# badge.net
KiCad netlist of a schematic drawn in EAGLE
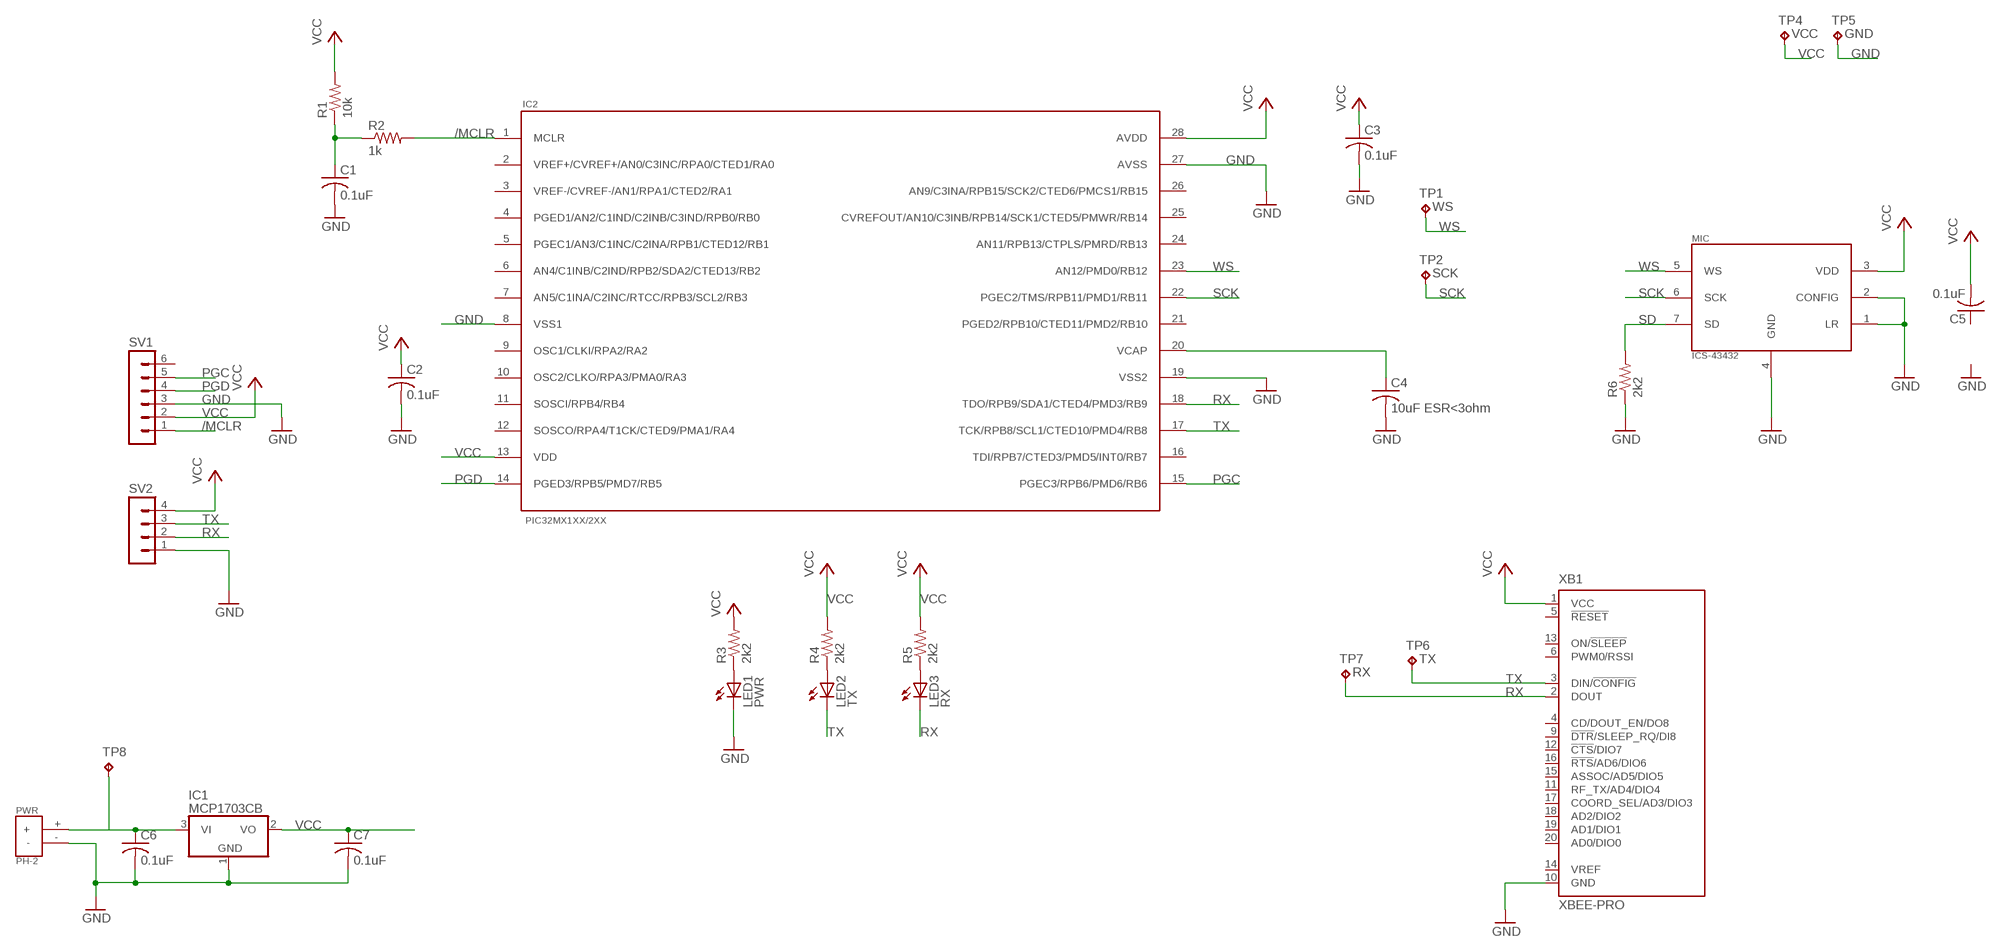
[diagram p0: schematic, sheet 1]

(export (version "E")
  (design (tool "Eeschema 10.0.6"))
  (components
    (comp (ref "C1")
      (value "0.1uF")
      (footprint "eagle-import:C0603")
      (libsource (lib "eagle-import") (part "C-USC0603"))
    )
    (comp (ref "C2")
      (value "0.1uF")
      (footprint "eagle-import:C0603")
      (libsource (lib "eagle-import") (part "C-USC0603"))
    )
    (comp (ref "C3")
      (value "0.1uF")
      (footprint "eagle-import:C0603")
      (libsource (lib "eagle-import") (part "C-USC0603"))
    )
    (comp (ref "C4")
      (value "10uF ESR<3ohm")
      (footprint "eagle-import:C0603")
      (libsource (lib "eagle-import") (part "C-USC0603"))
    )
    (comp (ref "C5")
      (value "0.1uF")
      (footprint "eagle-import:C0603")
      (libsource (lib "eagle-import") (part "C-USC0603"))
    )
    (comp (ref "C6")
      (value "0.1uF")
      (footprint "eagle-import:C0603")
      (libsource (lib "eagle-import") (part "C-USC0603"))
    )
    (comp (ref "C7")
      (value "0.1uF")
      (footprint "eagle-import:C0603")
      (libsource (lib "eagle-import") (part "C-USC0603"))
    )
    (comp (ref "IC1")
      (value "MCP1703CB")
      (footprint "eagle-import:SOT23")
      (libsource (lib "eagle-import") (part "MCP1703CB"))
    )
    (comp (ref "IC2")
      (value "PIC32MX1XX/2XX")
      (footprint "eagle-import:SOIC-28")
      (libsource (lib "eagle-import") (part "PIC32MX1XX/2XX"))
    )
    (comp (ref "LED1")
      (value "PWR")
      (footprint "eagle-import:CHIP-LED0603")
      (libsource (lib "eagle-import") (part "LEDCHIP-LED0603"))
    )
    (comp (ref "LED2")
      (value "TX")
      (footprint "eagle-import:CHIP-LED0603")
      (libsource (lib "eagle-import") (part "LEDCHIP-LED0603"))
    )
    (comp (ref "LED3")
      (value "RX")
      (footprint "eagle-import:CHIP-LED0603")
      (libsource (lib "eagle-import") (part "LEDCHIP-LED0603"))
    )
    (comp (ref "MIC")
      (value "ICS-43432")
      (footprint "eagle-import:ICS-43432")
      (libsource (lib "eagle-import") (part "ICS-43432"))
    )
    (comp (ref "PWR")
      (value "PH-2")
      (footprint "eagle-import:PH-2")
      (libsource (lib "eagle-import") (part "PH-2"))
    )
    (comp (ref "R1")
      (value "10k")
      (footprint "eagle-import:R0603")
      (libsource (lib "eagle-import") (part "R-US_R0603"))
    )
    (comp (ref "R2")
      (value "1k")
      (footprint "eagle-import:R0603")
      (libsource (lib "eagle-import") (part "R-US_R0603"))
    )
    (comp (ref "R3")
      (value "2k2")
      (footprint "eagle-import:R0603")
      (libsource (lib "eagle-import") (part "R-US_R0603"))
    )
    (comp (ref "R4")
      (value "2k2")
      (footprint "eagle-import:R0603")
      (libsource (lib "eagle-import") (part "R-US_R0603"))
    )
    (comp (ref "R5")
      (value "2k2")
      (footprint "eagle-import:R0603")
      (libsource (lib "eagle-import") (part "R-US_R0603"))
    )
    (comp (ref "R6")
      (value "2k2")
      (footprint "eagle-import:R0603")
      (libsource (lib "eagle-import") (part "R-US_R0603"))
    )
    (comp (ref "SV1")
      (value "MA06-1")
      (footprint "eagle-import:MA06-1")
      (libsource (lib "eagle-import") (part "MA06-1"))
    )
    (comp (ref "SV2")
      (value "MA04-1")
      (footprint "eagle-import:MA04-1")
      (libsource (lib "eagle-import") (part "MA04-1"))
    )
    (comp (ref "TP1")
      (value "TPPAD1-13")
      (footprint "eagle-import:P1-13")
      (fields (field (name "TP_SIGNAL_NAME") "WS"))
      (libsource (lib "eagle-import") (part "TPPAD1-13"))
    )
    (comp (ref "TP2")
      (value "TPPAD1-13")
      (footprint "eagle-import:P1-13")
      (fields (field (name "TP_SIGNAL_NAME") "SCK"))
      (libsource (lib "eagle-import") (part "TPPAD1-13"))
    )
    (comp (ref "TP4")
      (value "TPPAD1-13")
      (footprint "eagle-import:P1-13")
      (fields (field (name "TP_SIGNAL_NAME") "VCC"))
      (libsource (lib "eagle-import") (part "TPPAD1-13"))
    )
    (comp (ref "TP5")
      (value "TPPAD1-13")
      (footprint "eagle-import:P1-13")
      (fields (field (name "TP_SIGNAL_NAME") "GND"))
      (libsource (lib "eagle-import") (part "TPPAD1-13"))
    )
    (comp (ref "TP6")
      (value "TPPAD1-13")
      (footprint "eagle-import:P1-13")
      (fields (field (name "TP_SIGNAL_NAME") "TX"))
      (libsource (lib "eagle-import") (part "TPPAD1-13"))
    )
    (comp (ref "TP7")
      (value "TPPAD1-13")
      (footprint "eagle-import:P1-13")
      (fields (field (name "TP_SIGNAL_NAME") "RX"))
      (libsource (lib "eagle-import") (part "TPPAD1-13"))
    )
    (comp (ref "TP8")
      (value "TPPAD1-13")
      (footprint "eagle-import:P1-13")
      (fields (field (name "TP_SIGNAL_NAME") "PWR"))
      (libsource (lib "eagle-import") (part "TPPAD1-13"))
    )
    (comp (ref "XB1")
      (value "XBEE-PRO")
      (footprint "eagle-import:XBEE-PRO")
      (fields (field (name "MPN") "XBP24-AWI-001"))
      (libsource (lib "eagle-import") (part "XBEE-PRO"))
    )
  )
  (nets
    (net (code "1") (name "/PGC") (class "Default")
      (node (ref "IC2") (pin "15") (pinfunction "PGEC3/RPB6/PMD6/RB6_15") (pintype "bidirectional"))
      (node (ref "SV1") (pin "5") (pinfunction "5_5") (pintype "passive"))
    )
    (net (code "2") (name "/PGD") (class "Default")
      (node (ref "IC2") (pin "14") (pinfunction "PGED3/RPB5/PMD7/RB5_14") (pintype "bidirectional"))
      (node (ref "SV1") (pin "4") (pinfunction "4_4") (pintype "passive"))
    )
    (net (code "3") (name "/RX") (class "Default")
      (node (ref "IC2") (pin "18") (pinfunction "TDO/RPB9/SDA1/CTED4/PMD3/RB9_18") (pintype "bidirectional"))
      (node (ref "LED3") (pin "C") (pinfunction "C_C") (pintype "passive"))
      (node (ref "SV2") (pin "2") (pinfunction "2_2") (pintype "passive"))
      (node (ref "TP7") (pin "TP") (pinfunction "TP_TP") (pintype "input"))
      (node (ref "XB1") (pin "2") (pinfunction "DOUT_2") (pintype "output"))
    )
    (net (code "4") (name "/SCK") (class "Default")
      (node (ref "IC2") (pin "22") (pinfunction "PGEC2/TMS/RPB11/PMD1/RB11_22") (pintype "bidirectional"))
      (node (ref "MIC") (pin "6") (pinfunction "SCK_6") (pintype "bidirectional"))
      (node (ref "TP2") (pin "TP") (pinfunction "TP_TP") (pintype "input"))
    )
    (net (code "5") (name "/SD") (class "Default")
      (node (ref "MIC") (pin "7") (pinfunction "SD_7") (pintype "bidirectional"))
      (node (ref "R6") (pin "2") (pinfunction "2_2") (pintype "passive"))
    )
    (net (code "6") (name "/TX") (class "Default")
      (node (ref "IC2") (pin "17") (pinfunction "TCK/RPB8/SCL1/CTED10/PMD4/RB8_17") (pintype "bidirectional"))
      (node (ref "LED2") (pin "C") (pinfunction "C_C") (pintype "passive"))
      (node (ref "SV2") (pin "3") (pinfunction "3_3") (pintype "passive"))
      (node (ref "TP6") (pin "TP") (pinfunction "TP_TP") (pintype "input"))
      (node (ref "XB1") (pin "3") (pinfunction "DIN/~{CONFIG}_3") (pintype "input"))
    )
    (net (code "7") (name "/WS") (class "Default")
      (node (ref "IC2") (pin "23") (pinfunction "AN12/PMD0/RB12_23") (pintype "bidirectional"))
      (node (ref "MIC") (pin "5") (pinfunction "WS_5") (pintype "bidirectional"))
      (node (ref "TP1") (pin "TP") (pinfunction "TP_TP") (pintype "input"))
    )
    (net (code "8") (name "/{slash}MCLR") (class "Default")
      (node (ref "IC2") (pin "1") (pinfunction "MCLR_1") (pintype "bidirectional"))
      (node (ref "R2") (pin "2") (pinfunction "2_2") (pintype "passive"))
      (node (ref "SV1") (pin "1") (pinfunction "1_1") (pintype "passive"))
    )
    (net (code "9") (name "GND") (class "Default")
      (node (ref "C1") (pin "2") (pinfunction "2_2") (pintype "passive"))
      (node (ref "C2") (pin "2") (pinfunction "2_2") (pintype "passive"))
      (node (ref "C3") (pin "2") (pinfunction "2_2") (pintype "passive"))
      (node (ref "C4") (pin "2") (pinfunction "2_2") (pintype "passive"))
      (node (ref "C6") (pin "2") (pinfunction "2_2") (pintype "passive"))
      (node (ref "C7") (pin "2") (pinfunction "2_2") (pintype "passive"))
      (node (ref "IC1") (pin "1") (pinfunction "GND_1") (pintype "passive"))
      (node (ref "IC2") (pin "19") (pinfunction "VSS2_19") (pintype "bidirectional"))
      (node (ref "IC2") (pin "27") (pinfunction "AVSS_27") (pintype "bidirectional"))
      (node (ref "IC2") (pin "8") (pinfunction "VSS1_8") (pintype "bidirectional"))
      (node (ref "LED1") (pin "C") (pinfunction "C_C") (pintype "passive"))
      (node (ref "MIC") (pin "1") (pinfunction "LR_1") (pintype "bidirectional"))
      (node (ref "MIC") (pin "2") (pinfunction "CONFIG_2") (pintype "bidirectional"))
      (node (ref "MIC") (pin "4") (pinfunction "GND_4") (pintype "bidirectional"))
      (node (ref "PWR") (pin "-") (pinfunction "-_-") (pintype "bidirectional"))
      (node (ref "R6") (pin "1") (pinfunction "1_1") (pintype "passive"))
      (node (ref "SV1") (pin "3") (pinfunction "3_3") (pintype "passive"))
      (node (ref "SV2") (pin "1") (pinfunction "1_1") (pintype "passive"))
      (node (ref "TP5") (pin "TP") (pinfunction "TP_TP") (pintype "input"))
      (node (ref "XB1") (pin "10") (pinfunction "GND_10") (pintype "power_in"))
    )
    (net (code "10") (name "Net-(C1-Pad1)") (class "Default")
      (node (ref "C1") (pin "1") (pinfunction "1_1") (pintype "passive"))
      (node (ref "R1") (pin "1") (pinfunction "1_1") (pintype "passive"))
      (node (ref "R2") (pin "1") (pinfunction "1_1") (pintype "passive"))
    )
    (net (code "11") (name "Net-(IC1-VI)") (class "Default")
      (node (ref "C6") (pin "1") (pinfunction "1_1") (pintype "passive"))
      (node (ref "IC1") (pin "3") (pinfunction "VI_3") (pintype "input"))
      (node (ref "PWR") (pin "+") (pinfunction "+_+") (pintype "bidirectional"))
      (node (ref "TP8") (pin "TP") (pinfunction "TP_TP") (pintype "input"))
    )
    (net (code "12") (name "Net-(IC2-VCAP)") (class "Default")
      (node (ref "C4") (pin "1") (pinfunction "1_1") (pintype "passive"))
      (node (ref "IC2") (pin "20") (pinfunction "VCAP_20") (pintype "bidirectional"))
    )
    (net (code "13") (name "Net-(LED1-PadA)") (class "Default")
      (node (ref "LED1") (pin "A") (pinfunction "A_A") (pintype "passive"))
      (node (ref "R3") (pin "1") (pinfunction "1_1") (pintype "passive"))
    )
    (net (code "14") (name "Net-(LED2-PadA)") (class "Default")
      (node (ref "LED2") (pin "A") (pinfunction "A_A") (pintype "passive"))
      (node (ref "R4") (pin "1") (pinfunction "1_1") (pintype "passive"))
    )
    (net (code "15") (name "Net-(LED3-PadA)") (class "Default")
      (node (ref "LED3") (pin "A") (pinfunction "A_A") (pintype "passive"))
      (node (ref "R5") (pin "1") (pinfunction "1_1") (pintype "passive"))
    )
    (net (code "16") (name "VCC") (class "Default")
      (node (ref "C2") (pin "1") (pinfunction "1_1") (pintype "passive"))
      (node (ref "C3") (pin "1") (pinfunction "1_1") (pintype "passive"))
      (node (ref "C5") (pin "2") (pinfunction "2_2") (pintype "passive"))
      (node (ref "C7") (pin "1") (pinfunction "1_1") (pintype "passive"))
      (node (ref "IC1") (pin "2") (pinfunction "VO_2") (pintype "passive"))
      (node (ref "IC2") (pin "13") (pinfunction "VDD_13") (pintype "bidirectional"))
      (node (ref "IC2") (pin "28") (pinfunction "AVDD_28") (pintype "bidirectional"))
      (node (ref "MIC") (pin "3") (pinfunction "VDD_3") (pintype "bidirectional"))
      (node (ref "R1") (pin "2") (pinfunction "2_2") (pintype "passive"))
      (node (ref "R3") (pin "2") (pinfunction "2_2") (pintype "passive"))
      (node (ref "R4") (pin "2") (pinfunction "2_2") (pintype "passive"))
      (node (ref "R5") (pin "2") (pinfunction "2_2") (pintype "passive"))
      (node (ref "SV1") (pin "2") (pinfunction "2_2") (pintype "passive"))
      (node (ref "SV2") (pin "4") (pinfunction "4_4") (pintype "passive"))
      (node (ref "TP4") (pin "TP") (pinfunction "TP_TP") (pintype "input"))
      (node (ref "XB1") (pin "1") (pinfunction "VCC_1") (pintype "power_in"))
    )
    (net (code "17") (name "unconnected-(C5-Pad1)") (class "Default")
      (node (ref "C5") (pin "1") (pinfunction "1_1") (pintype "passive"))
    )
    (net (code "18") (name "unconnected-(IC2-AN4{slash}C1INB{slash}C2IND{slash}RPB2{slash}SDA2{slash}CTED13{slash}RB2-Pad6)") (class "Default")
      (node (ref "IC2") (pin "6") (pinfunction "AN4/C1INB/C2IND/RPB2/SDA2/CTED13/RB2_6") (pintype "bidirectional"))
    )
    (net (code "19") (name "unconnected-(IC2-AN5{slash}C1INA{slash}C2INC{slash}RTCC{slash}RPB3{slash}SCL2{slash}RB3-Pad7)") (class "Default")
      (node (ref "IC2") (pin "7") (pinfunction "AN5/C1INA/C2INC/RTCC/RPB3/SCL2/RB3_7") (pintype "bidirectional"))
    )
    (net (code "20") (name "unconnected-(IC2-AN9{slash}C3INA{slash}RPB15{slash}SCK2{slash}CTED6{slash}PMCS1{slash}RB15-Pad26)") (class "Default")
      (node (ref "IC2") (pin "26") (pinfunction "AN9/C3INA/RPB15/SCK2/CTED6/PMCS1/RB15_26") (pintype "bidirectional"))
    )
    (net (code "21") (name "unconnected-(IC2-AN11{slash}RPB13{slash}CTPLS{slash}PMRD{slash}RB13-Pad24)") (class "Default")
      (node (ref "IC2") (pin "24") (pinfunction "AN11/RPB13/CTPLS/PMRD/RB13_24") (pintype "bidirectional"))
    )
    (net (code "22") (name "unconnected-(IC2-CVREFOUT{slash}AN10{slash}C3INB{slash}RPB14{slash}SCK1{slash}CTED5{slash}PMWR{slash}RB14-Pad25)") (class "Default")
      (node (ref "IC2") (pin "25") (pinfunction "CVREFOUT/AN10/C3INB/RPB14/SCK1/CTED5/PMWR/RB14_25") (pintype "bidirectional"))
    )
    (net (code "23") (name "unconnected-(IC2-OSC1{slash}CLKI{slash}RPA2{slash}RA2-Pad9)") (class "Default")
      (node (ref "IC2") (pin "9") (pinfunction "OSC1/CLKI/RPA2/RA2_9") (pintype "bidirectional"))
    )
    (net (code "24") (name "unconnected-(IC2-OSC2{slash}CLKO{slash}RPA3{slash}PMA0{slash}RA3-Pad10)") (class "Default")
      (node (ref "IC2") (pin "10") (pinfunction "OSC2/CLKO/RPA3/PMA0/RA3_10") (pintype "bidirectional"))
    )
    (net (code "25") (name "unconnected-(IC2-PGEC1{slash}AN3{slash}C1INC{slash}C2INA{slash}RPB1{slash}CTED12{slash}RB1-Pad5)") (class "Default")
      (node (ref "IC2") (pin "5") (pinfunction "PGEC1/AN3/C1INC/C2INA/RPB1/CTED12/RB1_5") (pintype "bidirectional"))
    )
    (net (code "26") (name "unconnected-(IC2-PGED1{slash}AN2{slash}C1IND{slash}C2INB{slash}C3IND{slash}RPB0{slash}RB0-Pad4)") (class "Default")
      (node (ref "IC2") (pin "4") (pinfunction "PGED1/AN2/C1IND/C2INB/C3IND/RPB0/RB0_4") (pintype "bidirectional"))
    )
    (net (code "27") (name "unconnected-(IC2-PGED2{slash}RPB10{slash}CTED11{slash}PMD2{slash}RB10-Pad21)") (class "Default")
      (node (ref "IC2") (pin "21") (pinfunction "PGED2/RPB10/CTED11/PMD2/RB10_21") (pintype "bidirectional"))
    )
    (net (code "28") (name "unconnected-(IC2-SOSCI{slash}RPB4{slash}RB4-Pad11)") (class "Default")
      (node (ref "IC2") (pin "11") (pinfunction "SOSCI/RPB4/RB4_11") (pintype "bidirectional"))
    )
    (net (code "29") (name "unconnected-(IC2-SOSCO{slash}RPA4{slash}T1CK{slash}CTED9{slash}PMA1{slash}RA4-Pad12)") (class "Default")
      (node (ref "IC2") (pin "12") (pinfunction "SOSCO/RPA4/T1CK/CTED9/PMA1/RA4_12") (pintype "bidirectional"))
    )
    (net (code "30") (name "unconnected-(IC2-TDI{slash}RPB7{slash}CTED3{slash}PMD5{slash}INT0{slash}RB7-Pad16)") (class "Default")
      (node (ref "IC2") (pin "16") (pinfunction "TDI/RPB7/CTED3/PMD5/INT0/RB7_16") (pintype "bidirectional"))
    )
    (net (code "31") (name "unconnected-(IC2-VREF+{slash}CVREF+{slash}AN0{slash}C3INC{slash}RPA0{slash}CTED1{slash}RA0-Pad2)") (class "Default")
      (node (ref "IC2") (pin "2") (pinfunction "VREF+/CVREF+/AN0/C3INC/RPA0/CTED1/RA0_2") (pintype "bidirectional"))
    )
    (net (code "32") (name "unconnected-(IC2-VREF-{slash}CVREF-{slash}AN1{slash}RPA1{slash}CTED2{slash}RA1-Pad3)") (class "Default")
      (node (ref "IC2") (pin "3") (pinfunction "VREF-/CVREF-/AN1/RPA1/CTED2/RA1_3") (pintype "bidirectional"))
    )
    (net (code "33") (name "unconnected-(SV1-Pad6)") (class "Default")
      (node (ref "SV1") (pin "6") (pinfunction "6_6") (pintype "passive"))
    )
    (net (code "34") (name "unconnected-(XB1-AD0{slash}DIO0-Pad20)") (class "Default")
      (node (ref "XB1") (pin "20") (pinfunction "AD0/DIO0_20") (pintype "bidirectional"))
    )
    (net (code "35") (name "unconnected-(XB1-AD1{slash}DIO1-Pad19)") (class "Default")
      (node (ref "XB1") (pin "19") (pinfunction "AD1/DIO1_19") (pintype "bidirectional"))
    )
    (net (code "36") (name "unconnected-(XB1-AD2{slash}DIO2-Pad18)") (class "Default")
      (node (ref "XB1") (pin "18") (pinfunction "AD2/DIO2_18") (pintype "bidirectional"))
    )
    (net (code "37") (name "unconnected-(XB1-ASSOC{slash}AD5{slash}DIO5-Pad15)") (class "Default")
      (node (ref "XB1") (pin "15") (pinfunction "ASSOC/AD5/DIO5_15") (pintype "bidirectional"))
    )
    (net (code "38") (name "unconnected-(XB1-CD{slash}DOUT_EN{slash}DO8-Pad4)") (class "Default")
      (node (ref "XB1") (pin "4") (pinfunction "CD/DOUT_EN/DO8_4") (pintype "output"))
    )
    (net (code "39") (name "unconnected-(XB1-COORD_SEL{slash}AD3{slash}DIO3-Pad17)") (class "Default")
      (node (ref "XB1") (pin "17") (pinfunction "COORD_SEL/AD3/DIO3_17") (pintype "bidirectional"))
    )
    (net (code "40") (name "unconnected-(XB1-ON{slash}~{SLEEP}-Pad13)") (class "Default")
      (node (ref "XB1") (pin "13") (pinfunction "ON/~{SLEEP}_13") (pintype "output"))
    )
    (net (code "41") (name "unconnected-(XB1-PWM0{slash}RSSI-Pad6)") (class "Default")
      (node (ref "XB1") (pin "6") (pinfunction "PWM0/RSSI_6") (pintype "output"))
    )
    (net (code "42") (name "unconnected-(XB1-RF_TX{slash}AD4{slash}DIO4-Pad11)") (class "Default")
      (node (ref "XB1") (pin "11") (pinfunction "RF_TX/AD4/DIO4_11") (pintype "bidirectional"))
    )
    (net (code "43") (name "unconnected-(XB1-VREF-Pad14)") (class "Default")
      (node (ref "XB1") (pin "14") (pinfunction "VREF_14") (pintype "input"))
    )
    (net (code "44") (name "unconnected-(XB1-~{CTS}{slash}DIO7-Pad12)") (class "Default")
      (node (ref "XB1") (pin "12") (pinfunction "~{CTS}/DIO7_12") (pintype "bidirectional"))
    )
    (net (code "45") (name "unconnected-(XB1-~{DTR}{slash}SLEEP_RQ{slash}DI8-Pad9)") (class "Default")
      (node (ref "XB1") (pin "9") (pinfunction "~{DTR}/SLEEP_RQ/DI8_9") (pintype "bidirectional"))
    )
    (net (code "46") (name "unconnected-(XB1-~{RESET}-Pad5)") (class "Default")
      (node (ref "XB1") (pin "5") (pinfunction "~{RESET}_5") (pintype "input"))
    )
    (net (code "47") (name "unconnected-(XB1-~{RTS}{slash}AD6{slash}DIO6-Pad16)") (class "Default")
      (node (ref "XB1") (pin "16") (pinfunction "~{RTS}/AD6/DIO6_16") (pintype "bidirectional"))
    )
  )
)
